# Clock.net
KiCad netlist of a schematic drawn in EAGLE
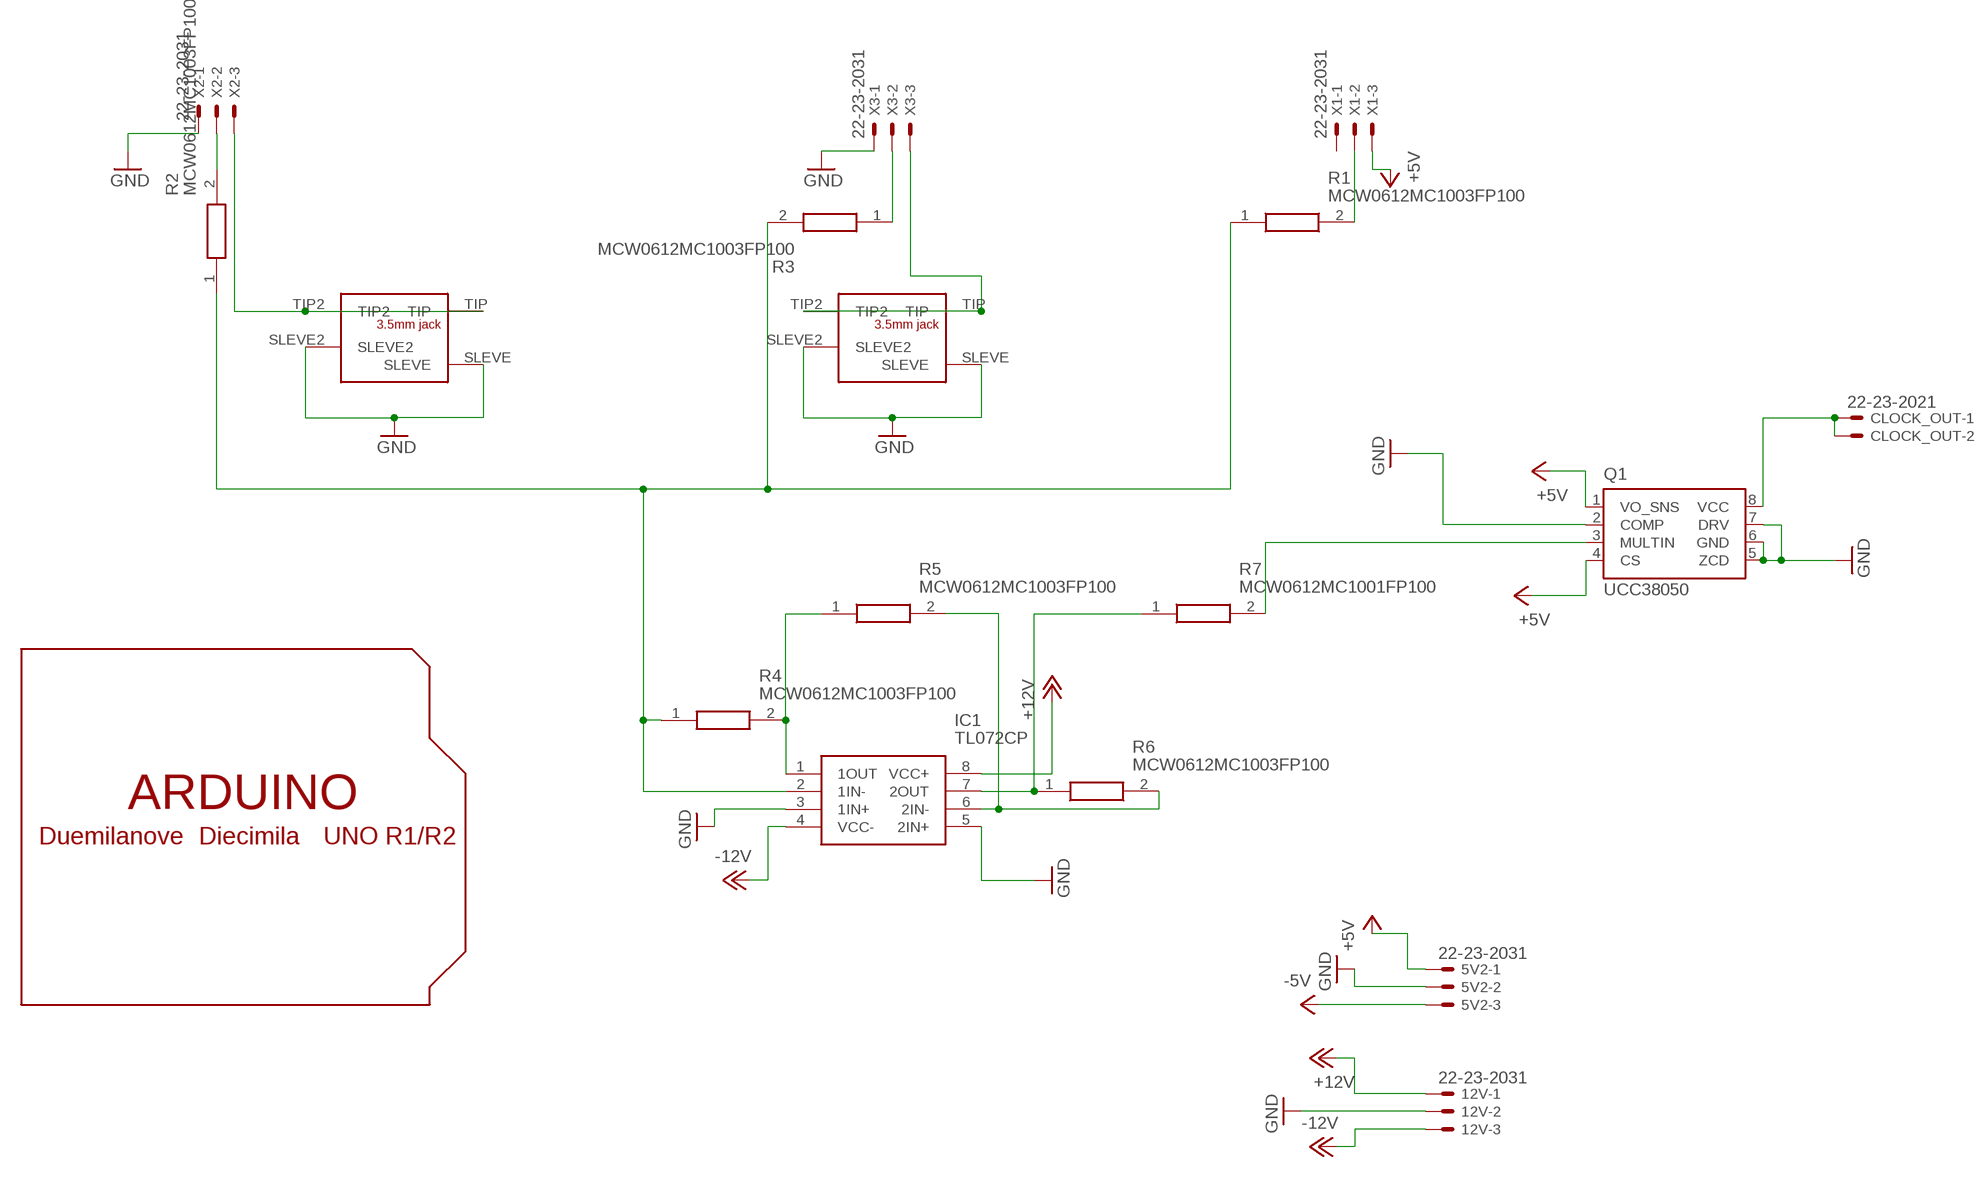
[diagram p0: schematic, sheet 1]

(export (version "E")
  (design (tool "Eeschema 10.0.6"))
  (components
    (comp (ref "5V2")
      (value "22-23-2031")
      (footprint "eagle-import:22-23-2031")
      (fields (field (name "MF") "MOLEX"))
      (libsource (lib "eagle-import") (part "22-23-2031"))
    )
    (comp (ref "12V")
      (value "22-23-2031")
      (footprint "eagle-import:22-23-2031")
      (fields (field (name "MF") "MOLEX"))
      (libsource (lib "eagle-import") (part "22-23-2031"))
    )
    (comp (ref "CLOCK_OUT")
      (value "22-23-2021")
      (footprint "eagle-import:22-23-2021")
      (fields (field (name "MF") "MOLEX"))
      (libsource (lib "eagle-import") (part "22-23-2021"))
    )
    (comp (ref "IC1")
      (value "TL072CP")
      (footprint "eagle-import:DIP794W53P254L959H508Q8N")
      (fields (field (name "MOUSER_PART_NUMBER") "595-TL072CP"))
      (libsource (lib "eagle-import") (part "TL072CP"))
    )
    (comp (ref "Q1")
      (value "UCC38050")
      (footprint "eagle-import:DIP-8")
      (libsource (lib "eagle-import") (part "UCC38050"))
    )
    (comp (ref "R1")
      (value "MCW0612MC1003FP100")
      (footprint "eagle-import:RESC1631X60N")
      (fields (field (name "MOUSER_PART_NUMBER") "594-MCW0612MC1003FP1"))
      (libsource (lib "eagle-import") (part "MCW0612MC1003FP100"))
    )
    (comp (ref "R2")
      (value "MCW0612MC1003FP100")
      (footprint "eagle-import:RESC1631X60N")
      (fields (field (name "MOUSER_PART_NUMBER") "594-MCW0612MC1003FP1"))
      (libsource (lib "eagle-import") (part "MCW0612MC1003FP100"))
    )
    (comp (ref "R3")
      (value "MCW0612MC1003FP100")
      (footprint "eagle-import:RESC1631X60N")
      (fields (field (name "MOUSER_PART_NUMBER") "594-MCW0612MC1003FP1"))
      (libsource (lib "eagle-import") (part "MCW0612MC1003FP100"))
    )
    (comp (ref "R4")
      (value "MCW0612MC1003FP100")
      (footprint "eagle-import:RESC1631X60N")
      (fields (field (name "MOUSER_PART_NUMBER") "594-MCW0612MC1003FP1"))
      (libsource (lib "eagle-import") (part "MCW0612MC1003FP100"))
    )
    (comp (ref "R5")
      (value "MCW0612MC1003FP100")
      (footprint "eagle-import:RESC1631X60N")
      (fields (field (name "MOUSER_PART_NUMBER") "594-MCW0612MC1003FP1"))
      (libsource (lib "eagle-import") (part "MCW0612MC1003FP100"))
    )
    (comp (ref "R6")
      (value "MCW0612MC1003FP100")
      (footprint "eagle-import:RESC1631X60N")
      (fields (field (name "MOUSER_PART_NUMBER") "594-MCW0612MC1003FP1"))
      (libsource (lib "eagle-import") (part "MCW0612MC1003FP100"))
    )
    (comp (ref "R7")
      (value "MCW0612MC1001FP100")
      (footprint "eagle-import:RESC1732X65N")
      (libsource (lib "eagle-import") (part "MCW0612MC1001FP100"))
    )
    (comp (ref "U$1")
      (value "ARDUINOHOLE")
      (footprint "eagle-import:ARDUINOHOLE")
      (libsource (lib "eagle-import") (part "ARDUINOHOLE"))
    )
    (comp (ref "U$2")
      (value "CL13845G")
      (footprint "eagle-import:CL13845G")
      (libsource (lib "eagle-import") (part "CL13845G"))
    )
    (comp (ref "U$3")
      (value "CL13845G")
      (footprint "eagle-import:CL13845G")
      (libsource (lib "eagle-import") (part "CL13845G"))
    )
    (comp (ref "X1")
      (value "22-23-2031")
      (footprint "eagle-import:22-23-2031")
      (fields (field (name "MF") "MOLEX"))
      (libsource (lib "eagle-import") (part "22-23-2031"))
    )
    (comp (ref "X2")
      (value "22-23-2031")
      (footprint "eagle-import:22-23-2031")
      (fields (field (name "MF") "MOLEX"))
      (libsource (lib "eagle-import") (part "22-23-2031"))
    )
    (comp (ref "X3")
      (value "22-23-2031")
      (footprint "eagle-import:22-23-2031")
      (fields (field (name "MF") "MOLEX"))
      (libsource (lib "eagle-import") (part "22-23-2031"))
    )
  )
  (nets
    (net (code "1") (name "+5V") (class "Default")
      (node (ref "5V2") (pin "1") (pinfunction "S_1") (pintype "passive"))
      (node (ref "Q1") (pin "1") (pinfunction "VO_SNS_1") (pintype "input"))
      (node (ref "Q1") (pin "4") (pinfunction "CS_4") (pintype "input"))
      (node (ref "X1") (pin "3") (pinfunction "S_3") (pintype "passive"))
    )
    (net (code "2") (name "+12V") (class "Default")
      (node (ref "12V") (pin "1") (pinfunction "S_1") (pintype "passive"))
      (node (ref "IC1") (pin "8") (pinfunction "VCC+_8") (pintype "power_in"))
    )
    (net (code "3") (name "-5V") (class "Default")
      (node (ref "5V2") (pin "3") (pinfunction "S_3") (pintype "passive"))
    )
    (net (code "4") (name "-12V") (class "Default")
      (node (ref "12V") (pin "3") (pinfunction "S_3") (pintype "passive"))
      (node (ref "IC1") (pin "4") (pinfunction "VCC-_4") (pintype "power_in"))
    )
    (net (code "5") (name "GND") (class "Default")
      (node (ref "12V") (pin "2") (pinfunction "S_2") (pintype "passive"))
      (node (ref "5V2") (pin "2") (pinfunction "S_2") (pintype "passive"))
      (node (ref "IC1") (pin "3") (pinfunction "1IN+_3") (pintype "input"))
      (node (ref "IC1") (pin "5") (pinfunction "2IN+_5") (pintype "input"))
      (node (ref "Q1") (pin "2") (pinfunction "COMP_2") (pintype "output"))
      (node (ref "Q1") (pin "5") (pinfunction "ZCD_5") (pintype "input"))
      (node (ref "Q1") (pin "6") (pinfunction "GND_6") (pintype "power_in"))
      (node (ref "Q1") (pin "7") (pinfunction "DRV_7") (pintype "output"))
      (node (ref "U$2") (pin "SLEVE") (pinfunction "SLEVE_SLEVE") (pintype "bidirectional"))
      (node (ref "U$2") (pin "SLEVE2") (pinfunction "SLEVE2_SLEVE2") (pintype "bidirectional"))
      (node (ref "U$3") (pin "SLEVE") (pinfunction "SLEVE_SLEVE") (pintype "bidirectional"))
      (node (ref "U$3") (pin "SLEVE2") (pinfunction "SLEVE2_SLEVE2") (pintype "bidirectional"))
      (node (ref "X2") (pin "1") (pinfunction "S_1") (pintype "passive"))
      (node (ref "X3") (pin "1") (pinfunction "S_1") (pintype "passive"))
    )
    (net (code "6") (name "Net-(CLOCK_OUTA-S)") (class "Default")
      (node (ref "CLOCK_OUT") (pin "1") (pinfunction "S_1") (pintype "passive"))
      (node (ref "CLOCK_OUT") (pin "2") (pinfunction "S_2") (pintype "passive"))
      (node (ref "Q1") (pin "8") (pinfunction "VCC_8") (pintype "power_in"))
    )
    (net (code "7") (name "Net-(IC1-1IN-)") (class "Default")
      (node (ref "IC1") (pin "2") (pinfunction "1IN-_2") (pintype "input"))
      (node (ref "R1") (pin "1") (pinfunction "1_1") (pintype "bidirectional"))
      (node (ref "R2") (pin "1") (pinfunction "1_1") (pintype "bidirectional"))
      (node (ref "R3") (pin "2") (pinfunction "2_2") (pintype "bidirectional"))
      (node (ref "R4") (pin "1") (pinfunction "1_1") (pintype "bidirectional"))
    )
    (net (code "8") (name "Net-(IC1-1OUT)") (class "Default")
      (node (ref "IC1") (pin "1") (pinfunction "1OUT_1") (pintype "output"))
      (node (ref "R4") (pin "2") (pinfunction "2_2") (pintype "bidirectional"))
      (node (ref "R5") (pin "1") (pinfunction "1_1") (pintype "bidirectional"))
    )
    (net (code "9") (name "Net-(IC1-2IN-)") (class "Default")
      (node (ref "IC1") (pin "6") (pinfunction "2IN-_6") (pintype "input"))
      (node (ref "R5") (pin "2") (pinfunction "2_2") (pintype "bidirectional"))
      (node (ref "R6") (pin "2") (pinfunction "2_2") (pintype "bidirectional"))
    )
    (net (code "10") (name "Net-(IC1-2OUT)") (class "Default")
      (node (ref "IC1") (pin "7") (pinfunction "2OUT_7") (pintype "output"))
      (node (ref "R6") (pin "1") (pinfunction "1_1") (pintype "bidirectional"))
      (node (ref "R7") (pin "1") (pinfunction "1_1") (pintype "bidirectional"))
    )
    (net (code "11") (name "Net-(Q1-MULTIN)") (class "Default")
      (node (ref "Q1") (pin "3") (pinfunction "MULTIN_3") (pintype "input"))
      (node (ref "R7") (pin "2") (pinfunction "2_2") (pintype "bidirectional"))
    )
    (net (code "12") (name "Net-(X1B-S)") (class "Default")
      (node (ref "R1") (pin "2") (pinfunction "2_2") (pintype "bidirectional"))
      (node (ref "X1") (pin "2") (pinfunction "S_2") (pintype "passive"))
    )
    (net (code "13") (name "Net-(X2B-S)") (class "Default")
      (node (ref "R2") (pin "2") (pinfunction "2_2") (pintype "bidirectional"))
      (node (ref "X2") (pin "2") (pinfunction "S_2") (pintype "passive"))
    )
    (net (code "14") (name "Net-(X2C-S)") (class "Default")
      (node (ref "U$2") (pin "TIP") (pinfunction "TIP_TIP") (pintype "bidirectional"))
      (node (ref "U$2") (pin "TIP2") (pinfunction "TIP2_TIP2") (pintype "bidirectional"))
      (node (ref "X2") (pin "3") (pinfunction "S_3") (pintype "passive"))
    )
    (net (code "15") (name "Net-(X3B-S)") (class "Default")
      (node (ref "R3") (pin "1") (pinfunction "1_1") (pintype "bidirectional"))
      (node (ref "X3") (pin "2") (pinfunction "S_2") (pintype "passive"))
    )
    (net (code "16") (name "Net-(X3C-S)") (class "Default")
      (node (ref "U$3") (pin "TIP") (pinfunction "TIP_TIP") (pintype "bidirectional"))
      (node (ref "U$3") (pin "TIP2") (pinfunction "TIP2_TIP2") (pintype "bidirectional"))
      (node (ref "X3") (pin "3") (pinfunction "S_3") (pintype "passive"))
    )
    (net (code "17") (name "unconnected-(X1A-S-Pad1)") (class "Default")
      (node (ref "X1") (pin "1") (pinfunction "S_1") (pintype "passive"))
    )
  )
)
